# LPS_Breakout.net
KiCad netlist of a schematic drawn in EAGLE
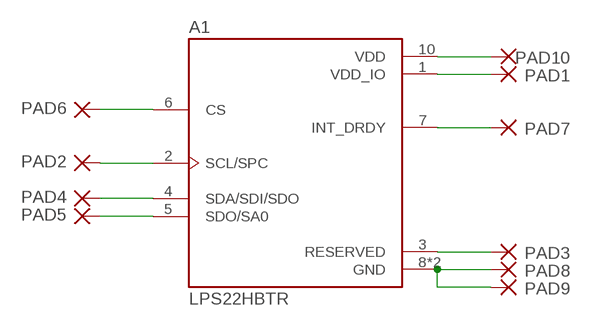
[diagram p0: schematic, sheet 1]

(export (version "E")
  (design (tool "Eeschema 10.0.6"))
  (components
    (comp (ref "A1")
      (value "LPS22HBTR")
      (footprint "eagle-import:PQFN50P200X200X80-10N")
      (fields (field (name "DIGI-KEY_PART_NUMBER") "497-16265-1-ND") (field (name "MF") "STMicroelectronics"))
      (libsource (lib "eagle-import") (part "LPS22HBTR"))
    )
    (comp (ref "PAD1")
      (value "1,6/0,8")
      (footprint "eagle-import:1,6_0,8")
      (libsource (lib "eagle-import") (part "1,6/0,8"))
    )
    (comp (ref "PAD2")
      (value "1,6/0,8")
      (footprint "eagle-import:1,6_0,8")
      (libsource (lib "eagle-import") (part "1,6/0,8"))
    )
    (comp (ref "PAD3")
      (value "1,6/0,8")
      (footprint "eagle-import:1,6_0,8")
      (libsource (lib "eagle-import") (part "1,6/0,8"))
    )
    (comp (ref "PAD4")
      (value "1,6/0,8")
      (footprint "eagle-import:1,6_0,8")
      (libsource (lib "eagle-import") (part "1,6/0,8"))
    )
    (comp (ref "PAD5")
      (value "1,6/0,8")
      (footprint "eagle-import:1,6_0,8")
      (libsource (lib "eagle-import") (part "1,6/0,8"))
    )
    (comp (ref "PAD6")
      (value "1,6/0,8")
      (footprint "eagle-import:1,6_0,8")
      (libsource (lib "eagle-import") (part "1,6/0,8"))
    )
    (comp (ref "PAD7")
      (value "1,6/0,8")
      (footprint "eagle-import:1,6_0,8")
      (libsource (lib "eagle-import") (part "1,6/0,8"))
    )
    (comp (ref "PAD8")
      (value "1,6/0,8")
      (footprint "eagle-import:1,6_0,8")
      (libsource (lib "eagle-import") (part "1,6/0,8"))
    )
    (comp (ref "PAD9")
      (value "1,6/0,8")
      (footprint "eagle-import:1,6_0,8")
      (libsource (lib "eagle-import") (part "1,6/0,8"))
    )
    (comp (ref "PAD10")
      (value "1,6/0,8")
      (footprint "eagle-import:1,6_0,8")
      (libsource (lib "eagle-import") (part "1,6/0,8"))
    )
  )
  (nets
    (net (code "1") (name "Net-(A1-CS)") (class "Default")
      (node (ref "A1") (pin "6") (pinfunction "CS_6") (pintype "input"))
      (node (ref "PAD6") (pin "1") (pinfunction "P_1") (pintype "passive"))
    )
    (net (code "2") (name "Net-(A1-INT_DRDY)") (class "Default")
      (node (ref "A1") (pin "7") (pinfunction "INT_DRDY_7") (pintype "output"))
      (node (ref "PAD7") (pin "1") (pinfunction "P_1") (pintype "passive"))
    )
    (net (code "3") (name "Net-(A1-RESERVED)") (class "Default")
      (node (ref "A1") (pin "3") (pinfunction "RESERVED_3") (pintype "passive"))
      (node (ref "PAD3") (pin "1") (pinfunction "P_1") (pintype "passive"))
    )
    (net (code "4") (name "Net-(A1-SCL{slash}SPC)") (class "Default")
      (node (ref "A1") (pin "2") (pinfunction "SCL/SPC_2") (pintype "input"))
      (node (ref "PAD2") (pin "1") (pinfunction "P_1") (pintype "passive"))
    )
    (net (code "5") (name "Net-(A1-SDA{slash}SDI{slash}SDO)") (class "Default")
      (node (ref "A1") (pin "4") (pinfunction "SDA/SDI/SDO_4") (pintype "bidirectional"))
      (node (ref "PAD4") (pin "1") (pinfunction "P_1") (pintype "passive"))
    )
    (net (code "6") (name "Net-(A1-SDO{slash}SA0)") (class "Default")
      (node (ref "A1") (pin "5") (pinfunction "SDO/SA0_5") (pintype "bidirectional"))
      (node (ref "PAD5") (pin "1") (pinfunction "P_1") (pintype "passive"))
    )
    (net (code "7") (name "Net-(A1-VDD)") (class "Default")
      (node (ref "A1") (pin "10") (pinfunction "VDD_10") (pintype "power_in"))
      (node (ref "PAD10") (pin "1") (pinfunction "P_1") (pintype "passive"))
    )
    (net (code "8") (name "Net-(A1-VDD_IO)") (class "Default")
      (node (ref "A1") (pin "1") (pinfunction "VDD_IO_1") (pintype "power_in"))
      (node (ref "PAD1") (pin "1") (pinfunction "P_1") (pintype "passive"))
    )
    (net (code "9") (name "Net-(PAD8-P)") (class "Default")
      (node (ref "A1") (pin "8") (pinfunction "GND_8") (pintype "power_in"))
      (node (ref "A1") (pin "9") (pinfunction "GND_9") (pintype "power_in"))
      (node (ref "PAD8") (pin "1") (pinfunction "P_1") (pintype "passive"))
      (node (ref "PAD9") (pin "1") (pinfunction "P_1") (pintype "passive"))
    )
  )
)
